# GCI_1_0.net
KiCad netlist of a schematic drawn in Altium Designer
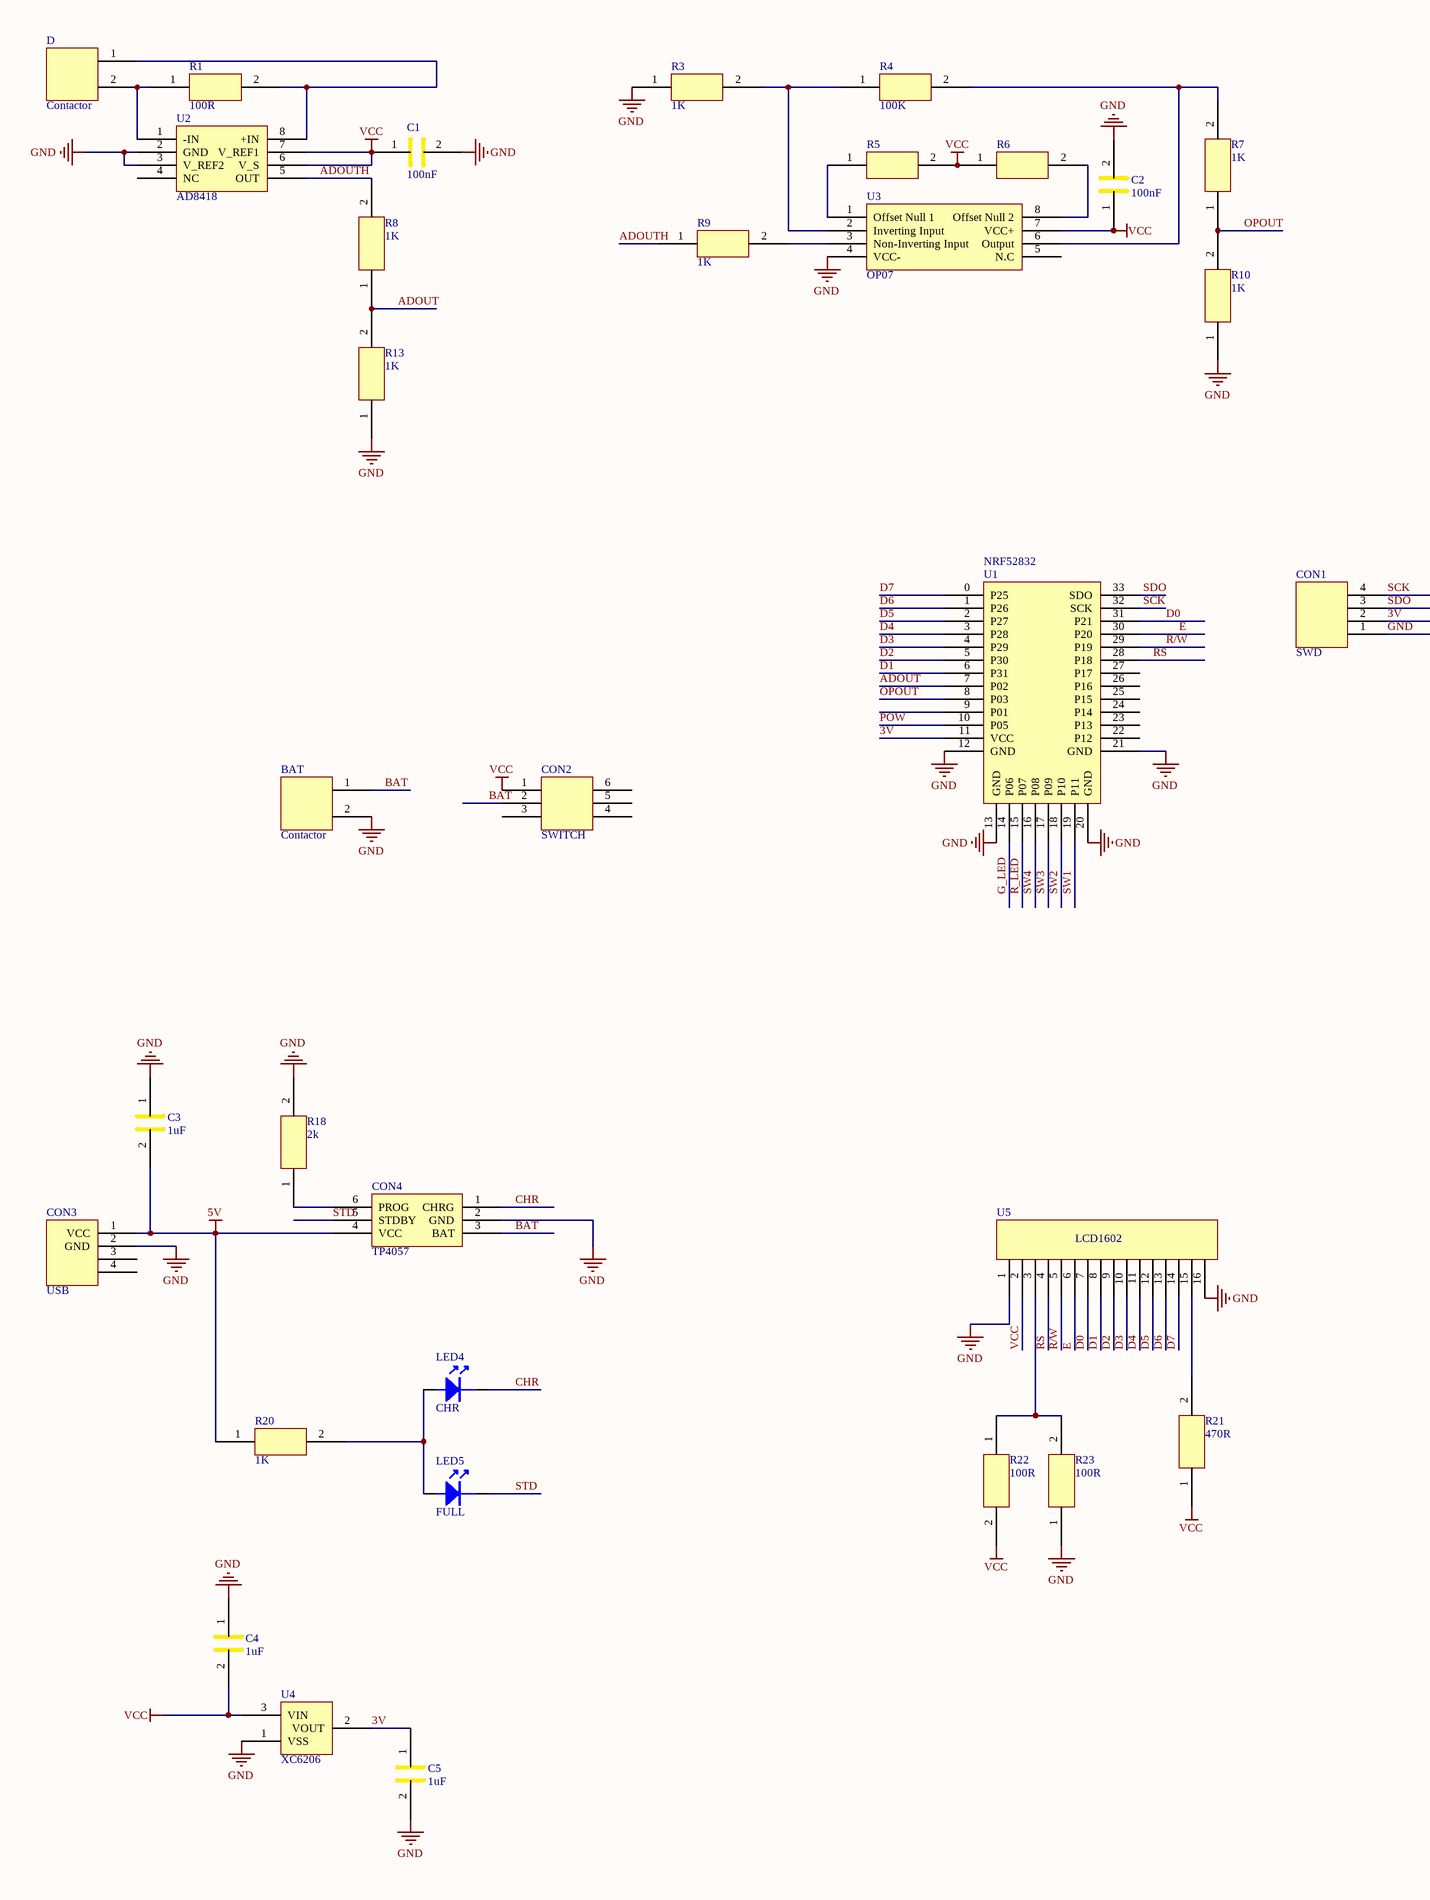
[diagram p0: GCI_1.0.SchDoc, left]
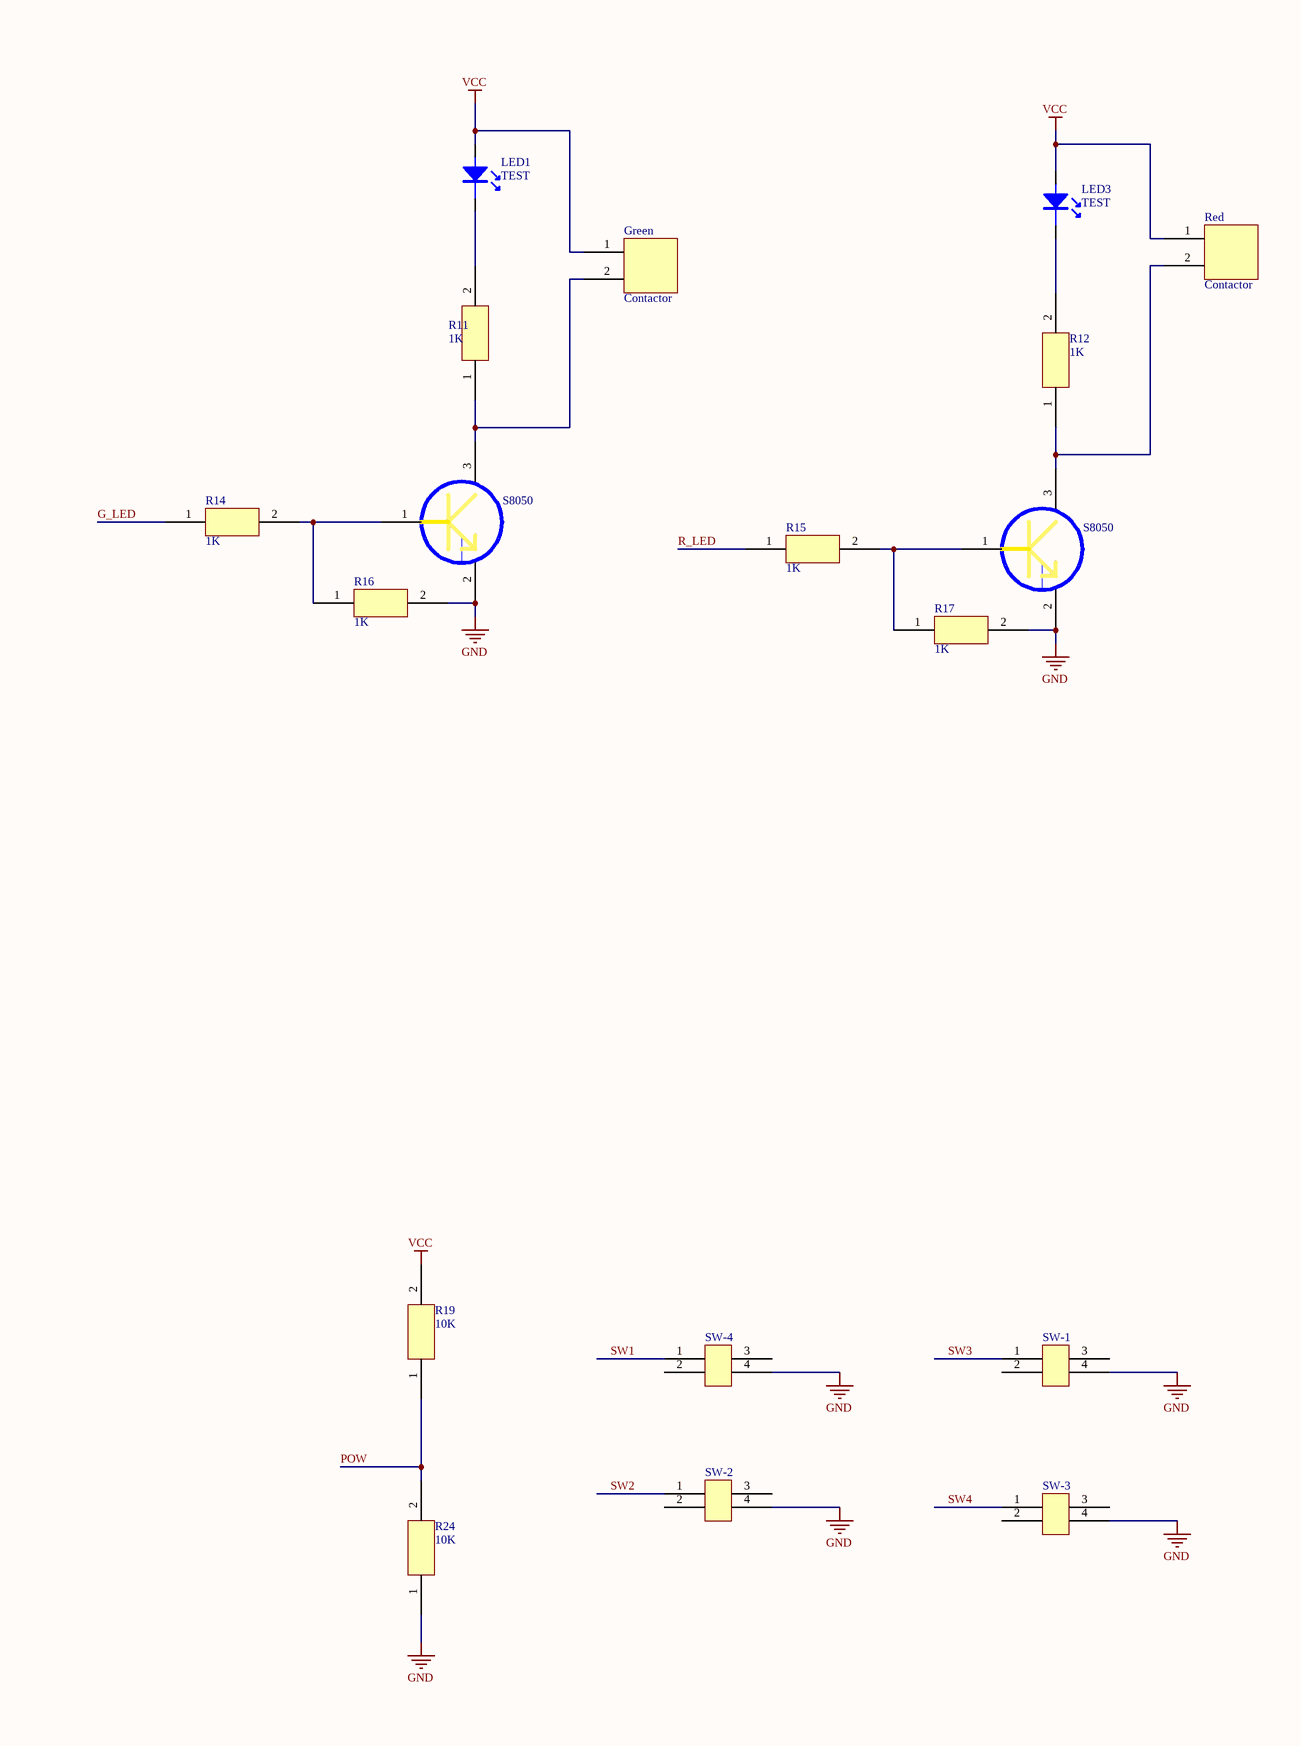
[diagram p1: GCI_1.0.SchDoc, right]

(export (version "E")
  (design (tool "Eeschema 10.0.6"))
  (components
    (comp (ref "*") (value "S8050") (footprint "SOT-23-S-1") (libsource (lib "Schlib1") (part "S8050")))
    (comp (ref "*3") (value "S8050") (footprint "SOT-23-S-1") (libsource (lib "Schlib1") (part "S8050")))
    (comp (ref "BAT") (value "Contactor") (libsource (lib "") (part "Contactor_1")))
    (comp (ref "C1") (value "100nF") (footprint "0603C") (libsource (lib "Schlib1") (part "Cap")))
    (comp (ref "C2") (value "100nF") (footprint "0603C") (libsource (lib "Schlib1") (part "Cap")))
    (comp (ref "C3") (value "1uF") (footprint "0603C") (libsource (lib "Schlib1") (part "Cap")))
    (comp (ref "C4") (value "1uF") (footprint "0603C") (libsource (lib "Schlib1") (part "Cap")))
    (comp (ref "C5") (value "1uF") (footprint "0603C") (libsource (lib "Schlib1") (part "Cap")))
    (comp (ref "CON1") (value "SWD") (footprint "SIP-4P") (libsource (lib "Schlib1") (part "Contactor_1")))
    (comp (ref "CON2") (value "SWITCH") (libsource (lib "Schlib1") (part "CON6")))
    (comp (ref "CON3") (value "USB") (footprint "USB") (libsource (lib "Schlib1") (part "USB")))
    (comp (ref "CON4")
      (value "TP4057")
      (footprint "SOT23-6-SMALL")
      (libsource (lib "Schlib1") (part "TP4057"))
    )
    (comp (ref "D") (value "Contactor") (libsource (lib "") (part "Contactor_1")))
    (comp (ref "Green") (value "Contactor") (libsource (lib "Schlib1") (part "Contactor")))
    (comp (ref "LED1") (value "TEST") (footprint "0603LED") (libsource (lib "LZMSCH库") (part "LED")))
    (comp (ref "LED3") (value "TEST") (footprint "0603LED") (libsource (lib "LZMSCH库") (part "LED")))
    (comp (ref "LED4") (value "CHR") (footprint "0603LED") (libsource (lib "LZMSCH库") (part "LED")))
    (comp (ref "LED5") (value "FULL") (footprint "0603LED") (libsource (lib "LZMSCH库") (part "LED")))
    (comp (ref "R1") (value "100R") (footprint "2512") (libsource (lib "Schlib1") (part "Resistance")))
    (comp (ref "R3") (value "1K") (footprint "0603R") (libsource (lib "Schlib1") (part "Resistance")))
    (comp (ref "R4") (value "100K") (footprint "0603R") (libsource (lib "Schlib1") (part "Resistance")))
    (comp (ref "R5") (value "~") (footprint "0603R") (libsource (lib "Schlib1") (part "Resistance")))
    (comp (ref "R6") (value "~") (footprint "0603R") (libsource (lib "Schlib1") (part "Resistance")))
    (comp (ref "R7") (value "1K") (footprint "0603R") (libsource (lib "") (part "Resistance_1")))
    (comp (ref "R8") (value "1K") (footprint "0603R") (libsource (lib "") (part "Resistance_1")))
    (comp (ref "R9") (value "1K") (footprint "0603R") (libsource (lib "Schlib1") (part "Resistance")))
    (comp (ref "R10") (value "1K") (footprint "0603R") (libsource (lib "") (part "Resistance_1")))
    (comp (ref "R11") (value "1K") (footprint "0603R") (libsource (lib "") (part "Resistance_1")))
    (comp (ref "R12") (value "1K") (footprint "0603R") (libsource (lib "") (part "Resistance_1")))
    (comp (ref "R13") (value "1K") (footprint "0603R") (libsource (lib "") (part "Resistance_1")))
    (comp (ref "R14") (value "1K") (footprint "0603R") (libsource (lib "Schlib1") (part "Resistance")))
    (comp (ref "R15") (value "1K") (footprint "0603R") (libsource (lib "Schlib1") (part "Resistance")))
    (comp (ref "R16") (value "1K") (footprint "0603R") (libsource (lib "Schlib1") (part "Resistance")))
    (comp (ref "R17") (value "1K") (footprint "0603R") (libsource (lib "Schlib1") (part "Resistance")))
    (comp (ref "R18") (value "2k") (footprint "0603R") (libsource (lib "") (part "Resistance_1")))
    (comp (ref "R19") (value "10K") (footprint "0603R") (libsource (lib "") (part "Resistance_1")))
    (comp (ref "R20") (value "1K") (footprint "0603R") (libsource (lib "Schlib1") (part "Resistance")))
    (comp (ref "R21") (value "470R") (footprint "0603R") (libsource (lib "") (part "Resistance_1")))
    (comp (ref "R22") (value "100R") (footprint "0603R") (libsource (lib "") (part "Resistance_2")))
    (comp (ref "R23") (value "100R") (footprint "0603R") (libsource (lib "") (part "Resistance_1")))
    (comp (ref "R24") (value "10K") (footprint "0603R") (libsource (lib "") (part "Resistance_1")))
    (comp (ref "Red") (value "Contactor") (libsource (lib "Schlib1") (part "Contactor")))
    (comp (ref "SW-1") (value "SW?") (footprint "Key4X4") (libsource (lib "Schlib1") (part "SW-4")))
    (comp (ref "SW-2") (value "SW?") (footprint "Key4X4") (libsource (lib "Schlib1") (part "SW-4")))
    (comp (ref "SW-3") (value "SW?") (footprint "Key4X4") (libsource (lib "Schlib1") (part "SW-4")))
    (comp (ref "SW-4") (value "SW?") (footprint "Key4X4") (libsource (lib "Schlib1") (part "SW-4")))
    (comp (ref "U1")
      (value "NRF52832")
      (footprint "NRF52832_MODEL")
      (libsource (lib "Schlib1") (part "NRF52832"))
    )
    (comp (ref "U2") (value "AD8418") (libsource (lib "Schlib1") (part "AD8418")))
    (comp (ref "U3") (value "OP07") (libsource (lib "Schlib1") (part "OP07")))
    (comp (ref "U4") (value "XC6206") (footprint "SOT-23-S-1") (libsource (lib "Schlib1") (part "XC6206")))
    (comp (ref "U5") (value "LCD1602") (footprint "LCD1602_S") (libsource (lib "Schlib1") (part "LCD1602")))
  )
  (nets
    (net (code "1") (name "/3V") (class "Default")
      (node (ref "C5") (pin "1") (pinfunction "*_1") (pintype "passive"))
      (node (ref "CON1") (pin "2") (pintype "passive"))
      (node (ref "U1") (pin "11") (pinfunction "VCC_11") (pintype "passive"))
      (node (ref "U4") (pin "2") (pinfunction "VOUT_2") (pintype "passive"))
    )
    (net (code "2") (name "/ADOUT") (class "Default")
      (node (ref "R13") (pin "2") (pinfunction "2_2") (pintype "passive"))
      (node (ref "R8") (pin "1") (pinfunction "1_1") (pintype "passive"))
      (node (ref "U1") (pin "7") (pinfunction "P02_7") (pintype "passive"))
    )
    (net (code "3") (name "/ADOUTH") (class "Default")
      (node (ref "R8") (pin "2") (pinfunction "2_2") (pintype "passive"))
      (node (ref "R9") (pin "1") (pinfunction "1_1") (pintype "passive"))
      (node (ref "U2") (pin "5") (pinfunction "OUT_5") (pintype "passive"))
    )
    (net (code "4") (name "/BAT") (class "Default")
      (node (ref "BAT") (pin "1") (pintype "passive"))
      (node (ref "CON2") (pin "2") (pintype "passive"))
      (node (ref "CON4") (pin "3") (pinfunction "BAT_3") (pintype "passive"))
    )
    (net (code "5") (name "/CHR") (class "Default")
      (node (ref "CON4") (pin "1") (pinfunction "CHRG_1") (pintype "passive"))
      (node (ref "LED4") (pin "K") (pinfunction "2_K") (pintype "passive"))
    )
    (net (code "6") (name "/D0") (class "Default")
      (node (ref "U1") (pin "31") (pinfunction "P21_31") (pintype "passive"))
      (node (ref "U5") (pin "7") (pinfunction "7_7") (pintype "passive"))
    )
    (net (code "7") (name "/D1") (class "Default")
      (node (ref "U1") (pin "6") (pinfunction "P31_6") (pintype "passive"))
      (node (ref "U5") (pin "8") (pinfunction "8_8") (pintype "passive"))
    )
    (net (code "8") (name "/D2") (class "Default")
      (node (ref "U1") (pin "5") (pinfunction "P30_5") (pintype "passive"))
      (node (ref "U5") (pin "9") (pinfunction "9_9") (pintype "passive"))
    )
    (net (code "9") (name "/D3") (class "Default")
      (node (ref "U1") (pin "4") (pinfunction "P29_4") (pintype "passive"))
      (node (ref "U5") (pin "10") (pinfunction "10_10") (pintype "passive"))
    )
    (net (code "10") (name "/D4") (class "Default")
      (node (ref "U1") (pin "3") (pinfunction "P28_3") (pintype "passive"))
      (node (ref "U5") (pin "11") (pinfunction "11_11") (pintype "passive"))
    )
    (net (code "11") (name "/D5") (class "Default")
      (node (ref "U1") (pin "2") (pinfunction "P27_2") (pintype "passive"))
      (node (ref "U5") (pin "12") (pinfunction "12_12") (pintype "passive"))
    )
    (net (code "12") (name "/D6") (class "Default")
      (node (ref "U1") (pin "1") (pinfunction "P26_1") (pintype "passive"))
      (node (ref "U5") (pin "13") (pinfunction "13_13") (pintype "passive"))
    )
    (net (code "13") (name "/D7") (class "Default")
      (node (ref "U1") (pin "0") (pinfunction "P25_0") (pintype "passive"))
      (node (ref "U5") (pin "14") (pinfunction "14_14") (pintype "passive"))
    )
    (net (code "14") (name "/E") (class "Default")
      (node (ref "U1") (pin "30") (pinfunction "P20_30") (pintype "passive"))
      (node (ref "U5") (pin "6") (pinfunction "6_6") (pintype "passive"))
    )
    (net (code "15") (name "/G_LED") (class "Default")
      (node (ref "R14") (pin "1") (pinfunction "1_1") (pintype "passive"))
      (node (ref "U1") (pin "14") (pinfunction "P06_14") (pintype "passive"))
    )
    (net (code "16") (name "/OPOUT") (class "Default")
      (node (ref "R10") (pin "2") (pinfunction "2_2") (pintype "passive"))
      (node (ref "R7") (pin "1") (pinfunction "1_1") (pintype "passive"))
      (node (ref "U1") (pin "8") (pinfunction "P03_8") (pintype "passive"))
    )
    (net (code "17") (name "/POW") (class "Default")
      (node (ref "R19") (pin "1") (pinfunction "1_1") (pintype "passive"))
      (node (ref "R24") (pin "2") (pinfunction "2_2") (pintype "passive"))
      (node (ref "U1") (pin "10") (pinfunction "P05_10") (pintype "passive"))
    )
    (net (code "18") (name "/RS") (class "Default")
      (node (ref "U1") (pin "28") (pinfunction "P18_28") (pintype "passive"))
      (node (ref "U5") (pin "4") (pinfunction "4_4") (pintype "passive"))
    )
    (net (code "19") (name "/R_LED") (class "Default")
      (node (ref "R15") (pin "1") (pinfunction "1_1") (pintype "passive"))
      (node (ref "U1") (pin "15") (pinfunction "P07_15") (pintype "passive"))
    )
    (net (code "20") (name "/R{slash}W") (class "Default")
      (node (ref "U1") (pin "29") (pinfunction "P19_29") (pintype "passive"))
      (node (ref "U5") (pin "5") (pinfunction "5_5") (pintype "passive"))
    )
    (net (code "21") (name "/SCK") (class "Default")
      (node (ref "CON1") (pin "4") (pintype "passive"))
      (node (ref "U1") (pin "32") (pinfunction "SCK_32") (pintype "passive"))
    )
    (net (code "22") (name "/SDO") (class "Default")
      (node (ref "CON1") (pin "3") (pintype "passive"))
      (node (ref "U1") (pin "33") (pinfunction "SDO_33") (pintype "passive"))
    )
    (net (code "23") (name "/STD") (class "Default")
      (node (ref "CON4") (pin "5") (pinfunction "STDBY_5") (pintype "passive"))
      (node (ref "LED5") (pin "K") (pinfunction "2_K") (pintype "passive"))
    )
    (net (code "24") (name "/SW1") (class "Default")
      (node (ref "U1") (pin "19") (pinfunction "P11_19") (pintype "passive"))
    )
    (net (code "25") (name "/SW2") (class "Default")
      (node (ref "U1") (pin "18") (pinfunction "P10_18") (pintype "passive"))
    )
    (net (code "26") (name "/SW3") (class "Default")
      (node (ref "U1") (pin "17") (pinfunction "P09_17") (pintype "passive"))
    )
    (net (code "27") (name "/SW4") (class "Default")
      (node (ref "U1") (pin "16") (pinfunction "P08_16") (pintype "passive"))
    )
    (net (code "28") (name "5V") (class "Default")
      (node (ref "C3") (pin "2") (pinfunction "*_2") (pintype "passive"))
      (node (ref "CON3") (pin "1") (pinfunction "VCC_1") (pintype "passive"))
      (node (ref "CON4") (pin "4") (pinfunction "VCC_4") (pintype "passive"))
      (node (ref "R20") (pin "1") (pinfunction "1_1") (pintype "passive"))
    )
    (net (code "29") (name "GND") (class "Default")
      (node (ref "*") (pin "2") (pintype "passive"))
      (node (ref "*3") (pin "2") (pintype "passive"))
      (node (ref "BAT") (pin "2") (pintype "passive"))
      (node (ref "C1") (pin "2") (pinfunction "*_2") (pintype "passive"))
      (node (ref "C2") (pin "2") (pinfunction "*_2") (pintype "passive"))
      (node (ref "C3") (pin "1") (pinfunction "*_1") (pintype "passive"))
      (node (ref "C4") (pin "1") (pinfunction "*_1") (pintype "passive"))
      (node (ref "C5") (pin "2") (pinfunction "*_2") (pintype "passive"))
      (node (ref "CON1") (pin "1") (pintype "passive"))
      (node (ref "CON3") (pin "2") (pinfunction "GND_2") (pintype "passive"))
      (node (ref "CON4") (pin "2") (pinfunction "GND_2") (pintype "passive"))
      (node (ref "R10") (pin "1") (pinfunction "1_1") (pintype "passive"))
      (node (ref "R13") (pin "1") (pinfunction "1_1") (pintype "passive"))
      (node (ref "R16") (pin "2") (pinfunction "2_2") (pintype "passive"))
      (node (ref "R17") (pin "2") (pinfunction "2_2") (pintype "passive"))
      (node (ref "R18") (pin "2") (pinfunction "2_2") (pintype "passive"))
      (node (ref "R23") (pin "1") (pinfunction "1_1") (pintype "passive"))
      (node (ref "R24") (pin "1") (pinfunction "1_1") (pintype "passive"))
      (node (ref "R3") (pin "1") (pinfunction "1_1") (pintype "passive"))
      (node (ref "SW-1") (pin "4") (pinfunction "*_4") (pintype "passive"))
      (node (ref "SW-2") (pin "4") (pinfunction "*_4") (pintype "passive"))
      (node (ref "SW-3") (pin "4") (pinfunction "*_4") (pintype "passive"))
      (node (ref "SW-4") (pin "4") (pinfunction "*_4") (pintype "passive"))
      (node (ref "U1") (pin "12") (pinfunction "GND_12") (pintype "passive"))
      (node (ref "U1") (pin "13") (pinfunction "GND_13") (pintype "passive"))
      (node (ref "U1") (pin "20") (pinfunction "GND_20") (pintype "passive"))
      (node (ref "U1") (pin "21") (pinfunction "GND_21") (pintype "passive"))
      (node (ref "U2") (pin "2") (pinfunction "GND_2") (pintype "passive"))
      (node (ref "U2") (pin "3") (pinfunction "V_REF2_3") (pintype "passive"))
      (node (ref "U3") (pin "4") (pinfunction "VCC-_4") (pintype "passive"))
      (node (ref "U4") (pin "1") (pinfunction "VSS_1") (pintype "passive"))
      (node (ref "U5") (pin "1") (pinfunction "1_1") (pintype "passive"))
      (node (ref "U5") (pin "16") (pinfunction "16_16") (pintype "passive"))
    )
    (net (code "30") (name "Net-(*-Pad3)") (class "Default")
      (node (ref "*") (pin "3") (pintype "passive"))
      (node (ref "Green") (pin "2") (pintype "passive"))
      (node (ref "R11") (pin "1") (pinfunction "1_1") (pintype "passive"))
    )
    (net (code "31") (name "Net-(*-VSS)") (class "Default")
      (node (ref "*") (pin "1") (pinfunction "VSS_1") (pintype "passive"))
      (node (ref "R14") (pin "2") (pinfunction "2_2") (pintype "passive"))
      (node (ref "R16") (pin "1") (pinfunction "1_1") (pintype "passive"))
    )
    (net (code "32") (name "Net-(*3-Pad3)") (class "Default")
      (node (ref "*3") (pin "3") (pintype "passive"))
      (node (ref "R12") (pin "1") (pinfunction "1_1") (pintype "passive"))
      (node (ref "Red") (pin "2") (pintype "passive"))
    )
    (net (code "33") (name "Net-(*3-VSS)") (class "Default")
      (node (ref "*3") (pin "1") (pinfunction "VSS_1") (pintype "passive"))
      (node (ref "R15") (pin "2") (pinfunction "2_2") (pintype "passive"))
      (node (ref "R17") (pin "1") (pinfunction "1_1") (pintype "passive"))
    )
    (net (code "34") (name "Net-(CON4-PROG)") (class "Default")
      (node (ref "CON4") (pin "6") (pinfunction "PROG_6") (pintype "passive"))
      (node (ref "R18") (pin "1") (pinfunction "1_1") (pintype "passive"))
    )
    (net (code "35") (name "Net-(LED1-2)") (class "Default")
      (node (ref "LED1") (pin "K") (pinfunction "2_K") (pintype "passive"))
      (node (ref "R11") (pin "2") (pinfunction "2_2") (pintype "passive"))
    )
    (net (code "36") (name "Net-(LED3-2)") (class "Default")
      (node (ref "LED3") (pin "K") (pinfunction "2_K") (pintype "passive"))
      (node (ref "R12") (pin "2") (pinfunction "2_2") (pintype "passive"))
    )
    (net (code "37") (name "Net-(LED4-1)") (class "Default")
      (node (ref "LED4") (pin "A") (pinfunction "1_A") (pintype "passive"))
      (node (ref "LED5") (pin "A") (pinfunction "1_A") (pintype "passive"))
      (node (ref "R20") (pin "2") (pinfunction "2_2") (pintype "passive"))
    )
    (net (code "38") (name "Net-(R21-Pad2)") (class "Default")
      (node (ref "R21") (pin "2") (pinfunction "2_2") (pintype "passive"))
      (node (ref "U5") (pin "15") (pinfunction "15_15") (pintype "passive"))
    )
    (net (code "39") (name "Net-(R22-Pad1)") (class "Default")
      (node (ref "R22") (pin "1") (pinfunction "1_1") (pintype "passive"))
      (node (ref "R23") (pin "2") (pinfunction "2_2") (pintype "passive"))
      (node (ref "U5") (pin "3") (pinfunction "3_3") (pintype "passive"))
    )
    (net (code "40") (name "Net-(U2-+IN)") (class "Default")
      (node (ref "D") (pin "1") (pintype "passive"))
      (node (ref "R1") (pin "2") (pinfunction "2_2") (pintype "passive"))
      (node (ref "U2") (pin "8") (pinfunction "+IN_8") (pintype "passive"))
    )
    (net (code "41") (name "Net-(U2--IN)") (class "Default")
      (node (ref "D") (pin "2") (pintype "passive"))
      (node (ref "R1") (pin "1") (pinfunction "1_1") (pintype "passive"))
      (node (ref "U2") (pin "1") (pinfunction "-IN_1") (pintype "passive"))
    )
    (net (code "42") (name "Net-(U3-Inverting_Input)") (class "Default")
      (node (ref "R3") (pin "2") (pinfunction "2_2") (pintype "passive"))
      (node (ref "R4") (pin "1") (pinfunction "1_1") (pintype "passive"))
      (node (ref "U3") (pin "2") (pinfunction "Inverting_Input_2") (pintype "passive"))
    )
    (net (code "43") (name "Net-(U3-Non-Inverting_Input)") (class "Default")
      (node (ref "R9") (pin "2") (pinfunction "2_2") (pintype "passive"))
      (node (ref "U3") (pin "3") (pinfunction "Non-Inverting_Input_3") (pintype "passive"))
    )
    (net (code "44") (name "Net-(U3-Offset_Null_1)") (class "Default")
      (node (ref "R5") (pin "1") (pinfunction "1_1") (pintype "passive"))
      (node (ref "U3") (pin "1") (pinfunction "Offset_Null_1_1") (pintype "passive"))
    )
    (net (code "45") (name "Net-(U3-Offset_Null_2)") (class "Default")
      (node (ref "R6") (pin "2") (pinfunction "2_2") (pintype "passive"))
      (node (ref "U3") (pin "8") (pinfunction "Offset_Null_2_8") (pintype "passive"))
    )
    (net (code "46") (name "Net-(U3-Output)") (class "Default")
      (node (ref "R4") (pin "2") (pinfunction "2_2") (pintype "passive"))
      (node (ref "R7") (pin "2") (pinfunction "2_2") (pintype "passive"))
      (node (ref "U3") (pin "6") (pinfunction "Output_6") (pintype "passive"))
    )
    (net (code "47") (name "VCC") (class "Default")
      (node (ref "C1") (pin "1") (pinfunction "*_1") (pintype "passive"))
      (node (ref "C2") (pin "1") (pinfunction "*_1") (pintype "passive"))
      (node (ref "C4") (pin "2") (pinfunction "*_2") (pintype "passive"))
      (node (ref "CON2") (pin "1") (pintype "passive"))
      (node (ref "Green") (pin "1") (pintype "passive"))
      (node (ref "LED1") (pin "A") (pinfunction "1_A") (pintype "passive"))
      (node (ref "LED3") (pin "A") (pinfunction "1_A") (pintype "passive"))
      (node (ref "R19") (pin "2") (pinfunction "2_2") (pintype "passive"))
      (node (ref "R21") (pin "1") (pinfunction "1_1") (pintype "passive"))
      (node (ref "R22") (pin "2") (pinfunction "2_2") (pintype "passive"))
      (node (ref "R5") (pin "2") (pinfunction "2_2") (pintype "passive"))
      (node (ref "R6") (pin "1") (pinfunction "1_1") (pintype "passive"))
      (node (ref "Red") (pin "1") (pintype "passive"))
      (node (ref "U2") (pin "6") (pinfunction "V_S_6") (pintype "passive"))
      (node (ref "U2") (pin "7") (pinfunction "V_REF1_7") (pintype "passive"))
      (node (ref "U3") (pin "7") (pinfunction "VCC+_7") (pintype "passive"))
      (node (ref "U4") (pin "3") (pinfunction "VIN_3") (pintype "passive"))
      (node (ref "U5") (pin "2") (pinfunction "2_2") (pintype "passive"))
    )
    (net (code "48") (name "unconnected-(CON2-Pad3)") (class "Default")
      (node (ref "CON2") (pin "3") (pintype "passive"))
    )
    (net (code "49") (name "unconnected-(CON2-Pad4)") (class "Default")
      (node (ref "CON2") (pin "4") (pintype "passive"))
    )
    (net (code "50") (name "unconnected-(CON2-Pad5)") (class "Default")
      (node (ref "CON2") (pin "5") (pintype "passive"))
    )
    (net (code "51") (name "unconnected-(CON2-Pad6)") (class "Default")
      (node (ref "CON2") (pin "6") (pintype "passive"))
    )
    (net (code "52") (name "unconnected-(CON3-Pad3)") (class "Default")
      (node (ref "CON3") (pin "3") (pintype "passive"))
    )
    (net (code "53") (name "unconnected-(CON3-Pad4)") (class "Default")
      (node (ref "CON3") (pin "4") (pintype "passive"))
    )
    (net (code "54") (name "unconnected-(SW-1-*-Pad1)") (class "Default")
      (node (ref "SW-1") (pin "1") (pinfunction "*_1") (pintype "passive"))
    )
    (net (code "55") (name "unconnected-(SW-1-*-Pad2)") (class "Default")
      (node (ref "SW-1") (pin "2") (pinfunction "*_2") (pintype "passive"))
    )
    (net (code "56") (name "unconnected-(SW-1-*-Pad3)") (class "Default")
      (node (ref "SW-1") (pin "3") (pinfunction "*_3") (pintype "passive"))
    )
    (net (code "57") (name "unconnected-(SW-2-*-Pad1)") (class "Default")
      (node (ref "SW-2") (pin "1") (pinfunction "*_1") (pintype "passive"))
    )
    (net (code "58") (name "unconnected-(SW-2-*-Pad2)") (class "Default")
      (node (ref "SW-2") (pin "2") (pinfunction "*_2") (pintype "passive"))
    )
    (net (code "59") (name "unconnected-(SW-2-*-Pad3)") (class "Default")
      (node (ref "SW-2") (pin "3") (pinfunction "*_3") (pintype "passive"))
    )
    (net (code "60") (name "unconnected-(SW-3-*-Pad1)") (class "Default")
      (node (ref "SW-3") (pin "1") (pinfunction "*_1") (pintype "passive"))
    )
    (net (code "61") (name "unconnected-(SW-3-*-Pad2)") (class "Default")
      (node (ref "SW-3") (pin "2") (pinfunction "*_2") (pintype "passive"))
    )
    (net (code "62") (name "unconnected-(SW-3-*-Pad3)") (class "Default")
      (node (ref "SW-3") (pin "3") (pinfunction "*_3") (pintype "passive"))
    )
    (net (code "63") (name "unconnected-(SW-4-*-Pad1)") (class "Default")
      (node (ref "SW-4") (pin "1") (pinfunction "*_1") (pintype "passive"))
    )
    (net (code "64") (name "unconnected-(SW-4-*-Pad2)") (class "Default")
      (node (ref "SW-4") (pin "2") (pinfunction "*_2") (pintype "passive"))
    )
    (net (code "65") (name "unconnected-(SW-4-*-Pad3)") (class "Default")
      (node (ref "SW-4") (pin "3") (pinfunction "*_3") (pintype "passive"))
    )
    (net (code "66") (name "unconnected-(U1-P01-Pad9)") (class "Default")
      (node (ref "U1") (pin "9") (pinfunction "P01_9") (pintype "passive"))
    )
    (net (code "67") (name "unconnected-(U1-P12-Pad22)") (class "Default")
      (node (ref "U1") (pin "22") (pinfunction "P12_22") (pintype "passive"))
    )
    (net (code "68") (name "unconnected-(U1-P13-Pad23)") (class "Default")
      (node (ref "U1") (pin "23") (pinfunction "P13_23") (pintype "passive"))
    )
    (net (code "69") (name "unconnected-(U1-P14-Pad24)") (class "Default")
      (node (ref "U1") (pin "24") (pinfunction "P14_24") (pintype "passive"))
    )
    (net (code "70") (name "unconnected-(U1-P15-Pad25)") (class "Default")
      (node (ref "U1") (pin "25") (pinfunction "P15_25") (pintype "passive"))
    )
    (net (code "71") (name "unconnected-(U1-P16-Pad26)") (class "Default")
      (node (ref "U1") (pin "26") (pinfunction "P16_26") (pintype "passive"))
    )
    (net (code "72") (name "unconnected-(U1-P17-Pad27)") (class "Default")
      (node (ref "U1") (pin "27") (pinfunction "P17_27") (pintype "passive"))
    )
    (net (code "73") (name "unconnected-(U2-NC-Pad4)") (class "Default")
      (node (ref "U2") (pin "4") (pinfunction "NC_4") (pintype "passive"))
    )
    (net (code "74") (name "unconnected-(U3-N.C-Pad5)") (class "Default")
      (node (ref "U3") (pin "5") (pinfunction "N.C_5") (pintype "passive"))
    )
  )
)
